# as5600.net
KiCad netlist of a schematic drawn in EAGLE
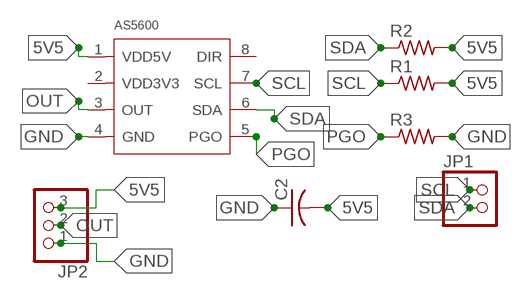
[diagram p0: schematic, sheet 1]

(export (version "E")
  (design (tool "Eeschema 10.0.6"))
  (components
    (comp (ref "AS5600")
      (value "AS5600AS5600")
      (footprint "eagle-import:AS5600")
      (fields (field (name "MF") "Ams AG") (field (name "MP") "AS5600"))
      (libsource (lib "eagle-import") (part "AS5600AS5600"))
    )
    (comp (ref "C2")
      (value "C-USC0603")
      (footprint "eagle-import:C0603")
      (libsource (lib "eagle-import") (part "C-USC0603"))
    )
    (comp (ref "JP1")
      (value "PINHD-1X2")
      (footprint "eagle-import:1X02")
      (libsource (lib "eagle-import") (part "PINHD-1X2"))
    )
    (comp (ref "JP2")
      (value "PINHD-1X3")
      (footprint "eagle-import:1X03")
      (libsource (lib "eagle-import") (part "PINHD-1X3"))
    )
    (comp (ref "R1")
      (value "R-US_R0603")
      (footprint "eagle-import:R0603")
      (libsource (lib "eagle-import") (part "R-US_R0603"))
    )
    (comp (ref "R2")
      (value "R-US_R0603")
      (footprint "eagle-import:R0603")
      (libsource (lib "eagle-import") (part "R-US_R0603"))
    )
    (comp (ref "R3")
      (value "R-US_R0603")
      (footprint "eagle-import:R0603")
      (libsource (lib "eagle-import") (part "R-US_R0603"))
    )
  )
  (nets
    (net (code "1") (name "5V5") (class "Default")
      (node (ref "AS5600") (pin "1") (pinfunction "VDD5V_1") (pintype "bidirectional"))
      (node (ref "C2") (pin "2") (pinfunction "2_2") (pintype "passive"))
      (node (ref "JP2") (pin "3") (pinfunction "3_3") (pintype "passive"))
      (node (ref "R1") (pin "2") (pinfunction "2_2") (pintype "passive"))
      (node (ref "R2") (pin "2") (pinfunction "2_2") (pintype "passive"))
    )
    (net (code "2") (name "GND") (class "Default")
      (node (ref "AS5600") (pin "4") (pinfunction "GND_4") (pintype "bidirectional"))
      (node (ref "C2") (pin "1") (pinfunction "1_1") (pintype "passive"))
      (node (ref "JP2") (pin "1") (pinfunction "1_1") (pintype "passive"))
      (node (ref "R3") (pin "2") (pinfunction "2_2") (pintype "passive"))
    )
    (net (code "3") (name "OUT") (class "Default")
      (node (ref "AS5600") (pin "3") (pinfunction "OUT_3") (pintype "bidirectional"))
      (node (ref "JP2") (pin "2") (pinfunction "2_2") (pintype "passive"))
    )
    (net (code "4") (name "PGO") (class "Default")
      (node (ref "AS5600") (pin "5") (pinfunction "PGO_5") (pintype "bidirectional"))
      (node (ref "R3") (pin "1") (pinfunction "1_1") (pintype "passive"))
    )
    (net (code "5") (name "SCL") (class "Default")
      (node (ref "AS5600") (pin "7") (pinfunction "SCL_7") (pintype "bidirectional"))
      (node (ref "JP1") (pin "1") (pinfunction "1_1") (pintype "passive"))
      (node (ref "R1") (pin "1") (pinfunction "1_1") (pintype "passive"))
    )
    (net (code "6") (name "SDA") (class "Default")
      (node (ref "AS5600") (pin "6") (pinfunction "SDA_6") (pintype "bidirectional"))
      (node (ref "JP1") (pin "2") (pinfunction "2_2") (pintype "passive"))
      (node (ref "R2") (pin "1") (pinfunction "1_1") (pintype "passive"))
    )
    (net (code "7") (name "unconnected-(AS5600-DIR-Pad8)") (class "Default")
      (node (ref "AS5600") (pin "8") (pinfunction "DIR_8") (pintype "bidirectional"))
    )
    (net (code "8") (name "unconnected-(AS5600-VDD3V3-Pad2)") (class "Default")
      (node (ref "AS5600") (pin "2") (pinfunction "VDD3V3_2") (pintype "bidirectional"))
    )
  )
)
